# Feather_M4_and_Supply.net
KiCad netlist of a schematic drawn in Altium Designer
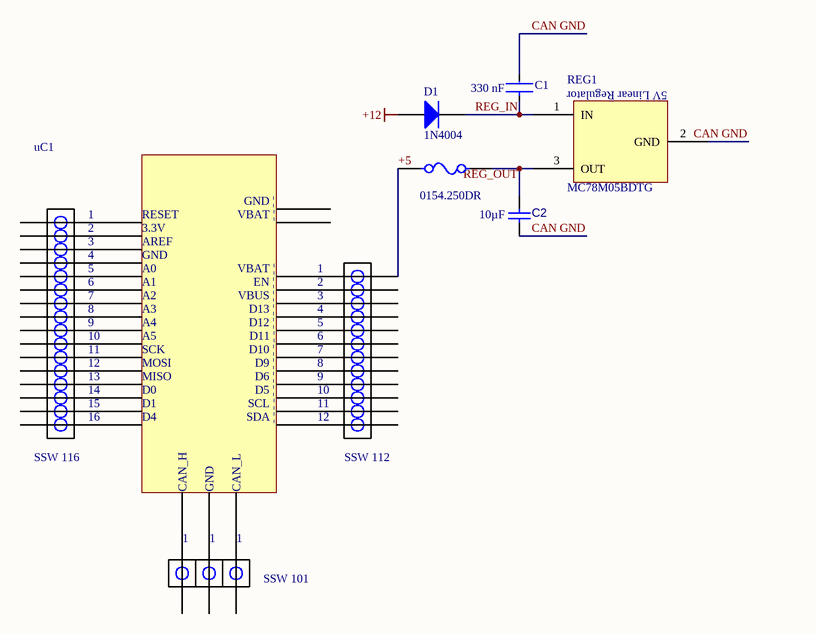
[diagram p0: Feather M4 and Supply.SchDoc]

(export (version "E")
  (design (tool "Eeschema 10.0.6"))
  (components
    (comp (ref "C1")
      (value "330 nF")
      (footprint "FP-CC0603-DA-MFG")
      (description "CAP CER 0.33UF 16V X7R 0603")
      (fields
        (field (name "OCTOPART") "https://octopart.com/cc0603krx7r7bb334-yageo-9291796")
        (field (name "MANUFACTURER") "YAGEO")
      )
      (libsource (lib "Altium Content Vault") (part "11868f565c42a9108669ba33697ecf6"))
    )
    (comp (ref "C2")
      (value "10µF")
      (footprint "CAPC0603(1608)100_L")
      (description "Chip Capacitor, 10µF +/-20%, 10V, 0603, Thickness 1 mm")
      (fields (field (name "TOLERANCE") "10%") (field (name "Comment") "Capacitor 10µF +/-20% 10V 0603"))
      (libsource (lib "WashU Racing") (part "CAP-NP-2"))
    )
    (comp (ref "D1")
      (value "1N4004")
      (footprint "FAIR-DO-41-2")
      (fields (field (name "MANUFACTURER") "Fairchild Semiconductor"))
      (libsource (lib "WashU Racing") (part "D-AK-2"))
    )
    (comp (ref "FUSE1")
      (value "0154.250DR")
      (footprint "FP-0154-MFG")
      (description "FUSE BOARD MNT 250MA 125VAC/VDC")
      (fields
        (field (name "MANUFACTURER") "Littelfuse")
        (field (name "OCTOPART") "https://octopart.com/0154.250dr-littelfuse-565851")
      )
      (libsource (lib "Altium Content Vault") (part "5bcf9b9f640e542cf0359d10258e979"))
    )
    (comp (ref "REG1")
      (value "MC78M05BDTG")
      (footprint "DPAK3")
      (description "IC REG LINEAR 5V 0.5A DPAK3")
      (libsource (lib "MC78M05BDTG") (part "MC78M05BDTG"))
    )
    (comp (ref "uC1")
      (value "CMP-001-0000-1")
      (footprint "Feather M4 CAN Express-Footprint-1")
      (description "Feather M4 Microcontroller with CAN")
      (libsource (lib "WashU Racing") (part "CMP-001-0000-1"))
    )
  )
  (nets
    (net (code "1") (name "+12") (class "Default")
      (node (ref "D1") (pin "1") (pinfunction "A_1") (pintype "passive"))
    )
    (net (code "2") (name "/+5") (class "Default")
      (node (ref "FUSE1") (pin "2") (pinfunction "2_2") (pintype "passive"))
      (node (ref "uC1") (pin "VBAT") (pinfunction "VBAT_VBAT") (pintype "passive"))
    )
    (net (code "3") (name "/CAN GND") (class "Default")
      (node (ref "C1") (pin "2") (pinfunction "2_2") (pintype "passive"))
      (node (ref "C2") (pin "2") (pinfunction "2_2") (pintype "passive"))
      (node (ref "REG1") (pin "2") (pinfunction "GND_2") (pintype "passive"))
    )
    (net (code "4") (name "/REG_IN") (class "Default")
      (node (ref "C1") (pin "1") (pinfunction "1_1") (pintype "passive"))
      (node (ref "D1") (pin "2") (pinfunction "K_2") (pintype "passive"))
      (node (ref "REG1") (pin "1") (pinfunction "IN_1") (pintype "passive"))
    )
    (net (code "5") (name "/REG_OUT") (class "Default")
      (node (ref "C2") (pin "1") (pinfunction "1_1") (pintype "passive"))
      (node (ref "FUSE1") (pin "1") (pinfunction "1_1") (pintype "passive"))
      (node (ref "REG1") (pin "3") (pinfunction "OUT_3") (pintype "passive"))
    )
    (net (code "6") (name "unconnected-(uC1-Pad3.3V)") (class "Default")
      (node (ref "uC1") (pin "3.3V") (pinfunction "3.3V_3.3V") (pintype "passive"))
    )
    (net (code "7") (name "unconnected-(uC1-PadA0)") (class "Default")
      (node (ref "uC1") (pin "A0") (pinfunction "A0_A0") (pintype "passive"))
    )
    (net (code "8") (name "unconnected-(uC1-PadA1)") (class "Default")
      (node (ref "uC1") (pin "A1") (pinfunction "A1_A1") (pintype "passive"))
    )
    (net (code "9") (name "unconnected-(uC1-PadA2)") (class "Default")
      (node (ref "uC1") (pin "A2") (pinfunction "A2_A2") (pintype "passive"))
    )
    (net (code "10") (name "unconnected-(uC1-PadA3)") (class "Default")
      (node (ref "uC1") (pin "A3") (pinfunction "A3_A3") (pintype "passive"))
    )
    (net (code "11") (name "unconnected-(uC1-PadA4)") (class "Default")
      (node (ref "uC1") (pin "A4") (pinfunction "A4_A4") (pintype "passive"))
    )
    (net (code "12") (name "unconnected-(uC1-PadA5)") (class "Default")
      (node (ref "uC1") (pin "A5") (pinfunction "A5_A5") (pintype "passive"))
    )
    (net (code "13") (name "unconnected-(uC1-PadAREF)") (class "Default")
      (node (ref "uC1") (pin "AREF") (pinfunction "AREF_AREF") (pintype "passive"))
    )
    (net (code "14") (name "unconnected-(uC1-PadCAN_H)") (class "Default")
      (node (ref "uC1") (pin "CAN_H") (pinfunction "CAN_H_CAN_H") (pintype "passive"))
    )
    (net (code "15") (name "unconnected-(uC1-PadCAN_L)") (class "Default")
      (node (ref "uC1") (pin "CAN_L") (pinfunction "CAN_L_CAN_L") (pintype "passive"))
    )
    (net (code "16") (name "unconnected-(uC1-PadD0)") (class "Default")
      (node (ref "uC1") (pin "D0") (pinfunction "D0_D0") (pintype "passive"))
    )
    (net (code "17") (name "unconnected-(uC1-PadD1)") (class "Default")
      (node (ref "uC1") (pin "D1") (pinfunction "D1_D1") (pintype "passive"))
    )
    (net (code "18") (name "unconnected-(uC1-PadD4)") (class "Default")
      (node (ref "uC1") (pin "D4") (pinfunction "D4_D4") (pintype "passive"))
    )
    (net (code "19") (name "unconnected-(uC1-PadD5)") (class "Default")
      (node (ref "uC1") (pin "D5") (pinfunction "D5_D5") (pintype "passive"))
    )
    (net (code "20") (name "unconnected-(uC1-PadD6)") (class "Default")
      (node (ref "uC1") (pin "D6") (pinfunction "D6_D6") (pintype "passive"))
    )
    (net (code "21") (name "unconnected-(uC1-PadD9)") (class "Default")
      (node (ref "uC1") (pin "D9") (pinfunction "D9_D9") (pintype "passive"))
    )
    (net (code "22") (name "unconnected-(uC1-PadD10)") (class "Default")
      (node (ref "uC1") (pin "D10") (pinfunction "D10_D10") (pintype "passive"))
    )
    (net (code "23") (name "unconnected-(uC1-PadD11)") (class "Default")
      (node (ref "uC1") (pin "D11") (pinfunction "D11_D11") (pintype "passive"))
    )
    (net (code "24") (name "unconnected-(uC1-PadD12)") (class "Default")
      (node (ref "uC1") (pin "D12") (pinfunction "D12_D12") (pintype "passive"))
    )
    (net (code "25") (name "unconnected-(uC1-PadD13)") (class "Default")
      (node (ref "uC1") (pin "D13") (pinfunction "D13_D13") (pintype "passive"))
    )
    (net (code "26") (name "unconnected-(uC1-PadEN)") (class "Default")
      (node (ref "uC1") (pin "EN") (pinfunction "EN_EN") (pintype "passive"))
    )
    (net (code "27") (name "unconnected-(uC1-PadGND)") (class "Default")
      (node (ref "uC1") (pin "GND") (pinfunction "GND_GND") (pintype "passive"))
    )
    (net (code "28") (name "unconnected-(uC1-PadGND)_1") (class "Default")
      (node (ref "uC1") (pin "GND") (pinfunction "GND_GND") (pintype "passive"))
    )
    (net (code "29") (name "unconnected-(uC1-PadMISO)") (class "Default")
      (node (ref "uC1") (pin "MISO") (pinfunction "MISO_MISO") (pintype "passive"))
    )
    (net (code "30") (name "unconnected-(uC1-PadMOSI)") (class "Default")
      (node (ref "uC1") (pin "MOSI") (pinfunction "MOSI_MOSI") (pintype "passive"))
    )
    (net (code "31") (name "unconnected-(uC1-PadRESET)") (class "Default")
      (node (ref "uC1") (pin "RESET") (pinfunction "RESET_RESET") (pintype "passive"))
    )
    (net (code "32") (name "unconnected-(uC1-PadSCK)") (class "Default")
      (node (ref "uC1") (pin "SCK") (pinfunction "SCK_SCK") (pintype "passive"))
    )
    (net (code "33") (name "unconnected-(uC1-PadSCL)") (class "Default")
      (node (ref "uC1") (pin "SCL") (pinfunction "SCL_SCL") (pintype "passive"))
    )
    (net (code "34") (name "unconnected-(uC1-PadSDA)") (class "Default")
      (node (ref "uC1") (pin "SDA") (pinfunction "SDA_SDA") (pintype "passive"))
    )
    (net (code "35") (name "unconnected-(uC1-PadVBUS)") (class "Default")
      (node (ref "uC1") (pin "VBUS") (pinfunction "VBUS_VBUS") (pintype "passive"))
    )
  )
)
